# S7G7_footprint_simplified_w_ethernet_v1p.net
KiCad netlist of a schematic drawn in EAGLE
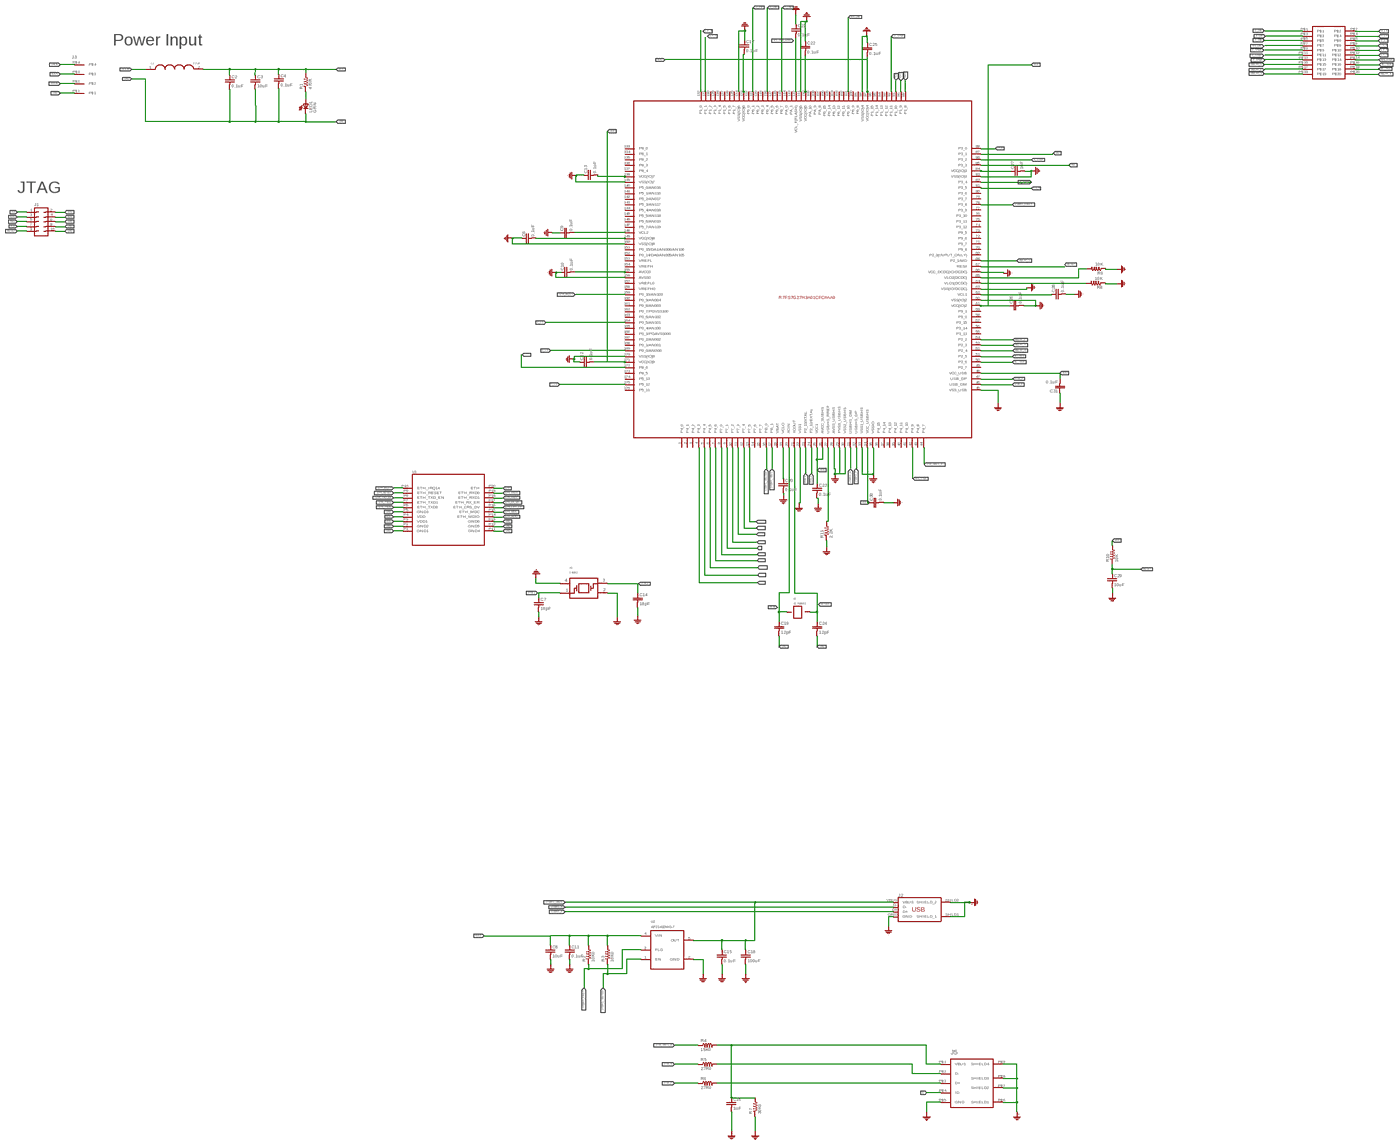
[diagram p0: schematic, sheet 1, overview]
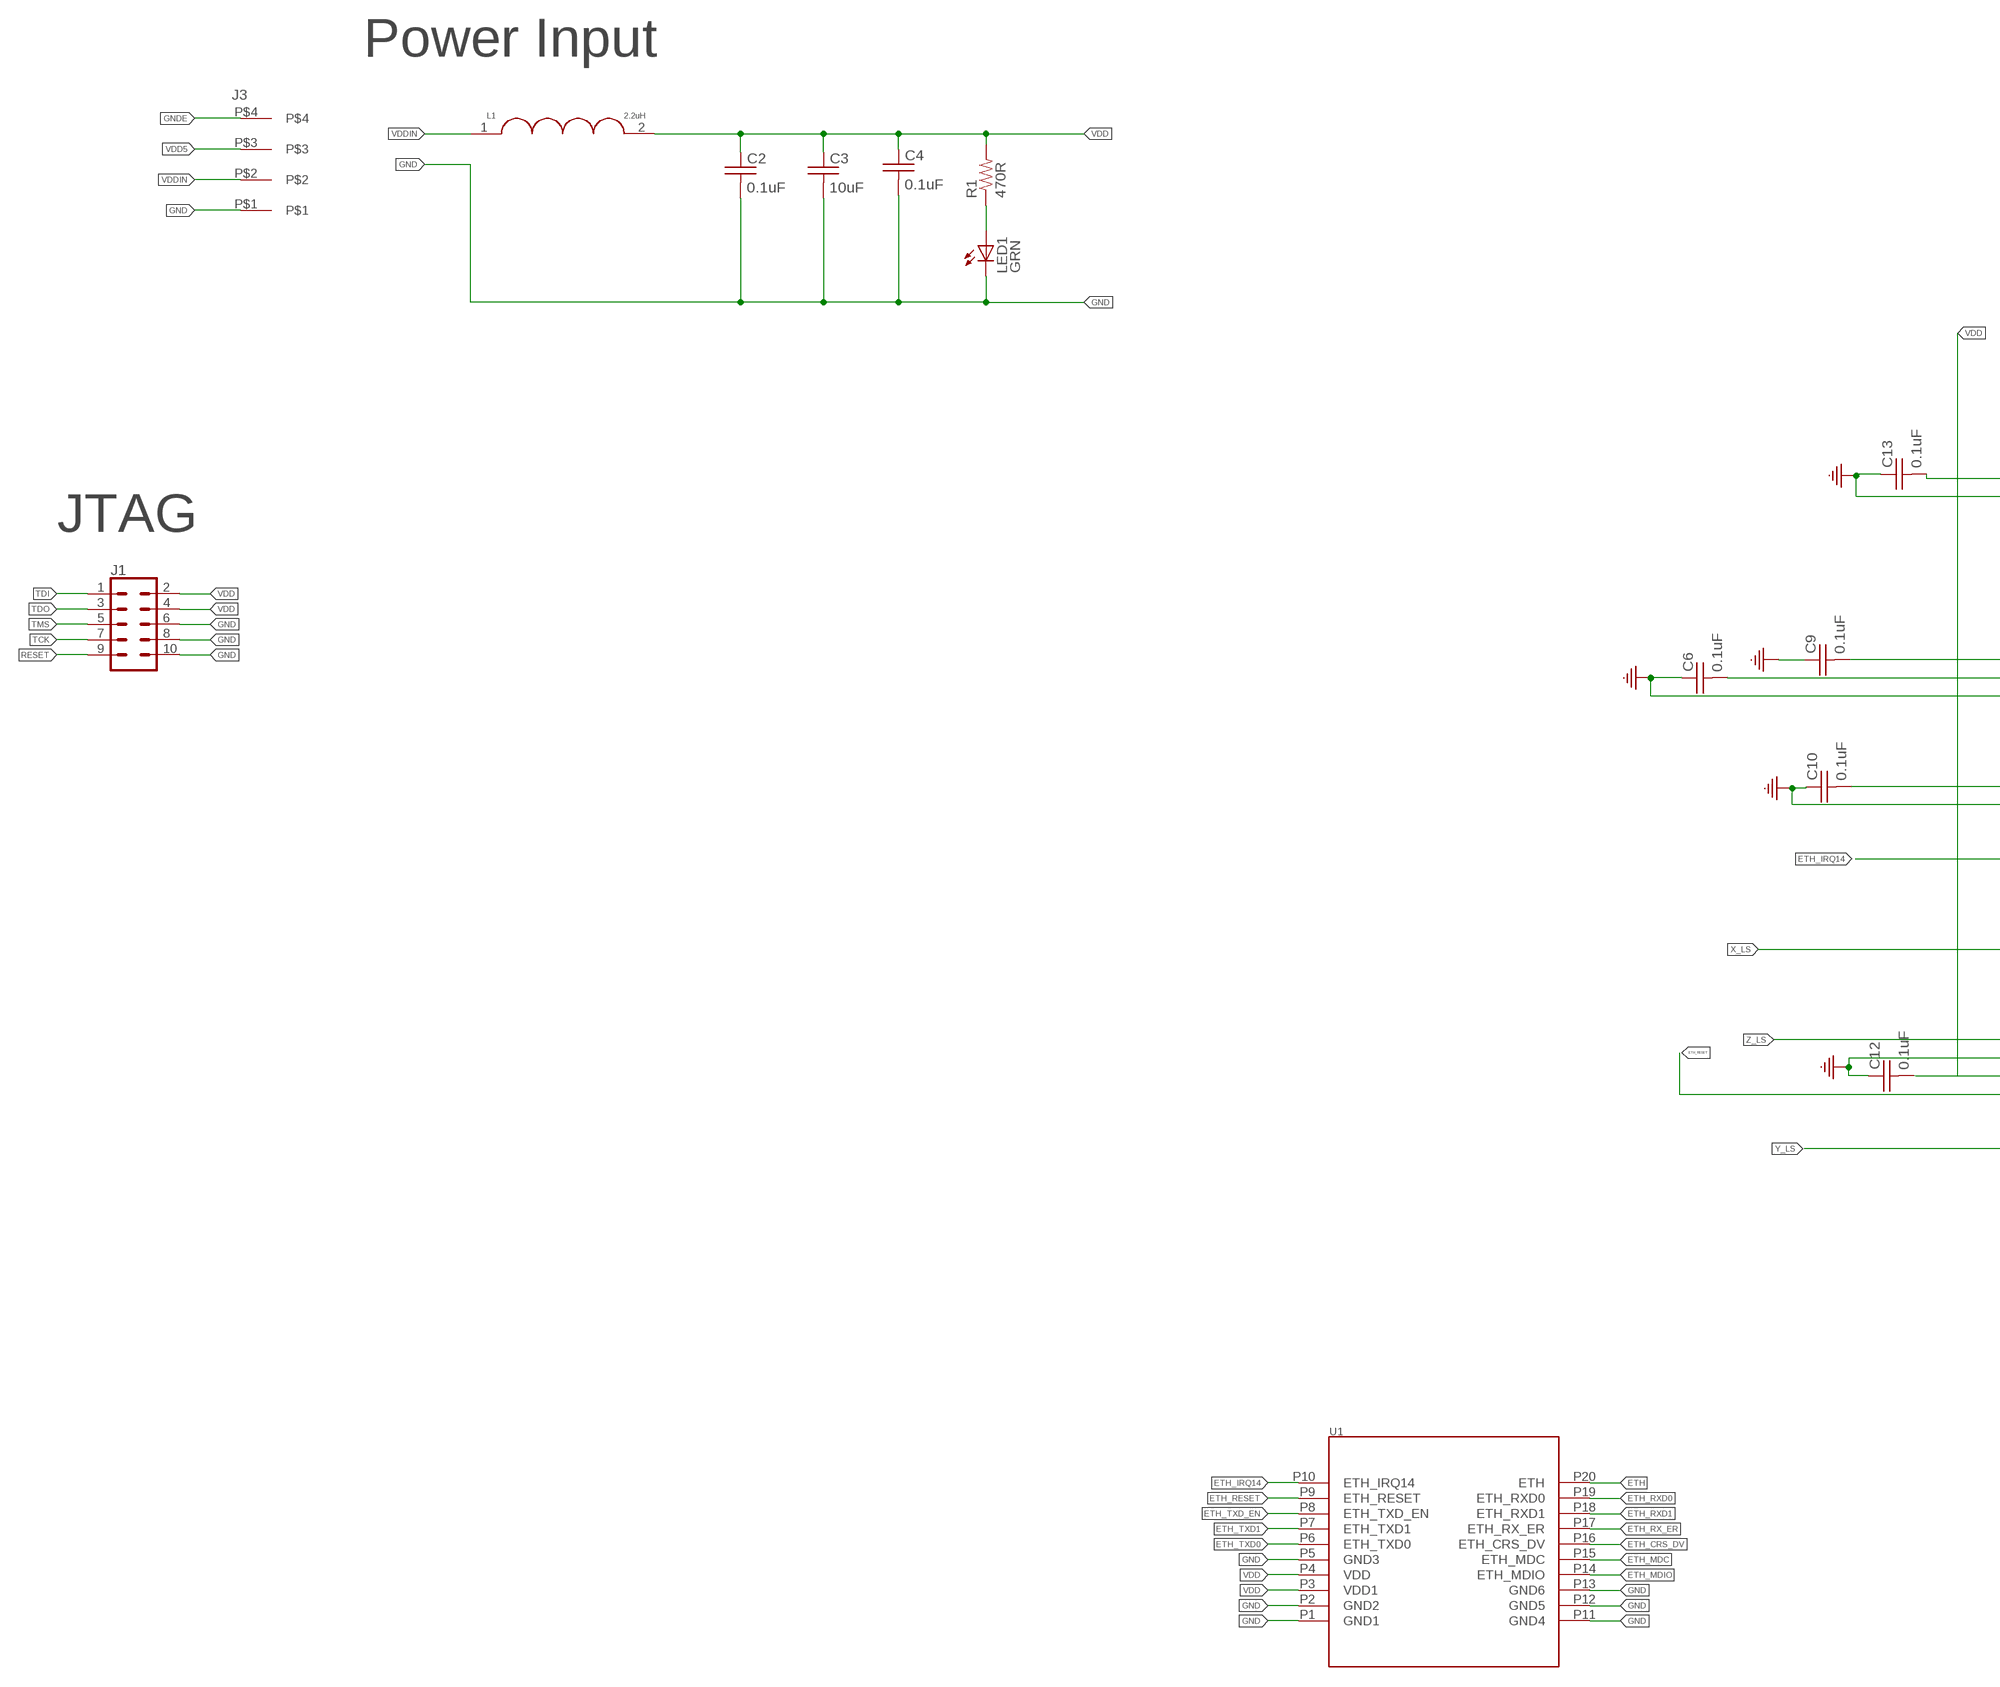
[diagram p1: schematic, sheet 1, part 1 of 4]
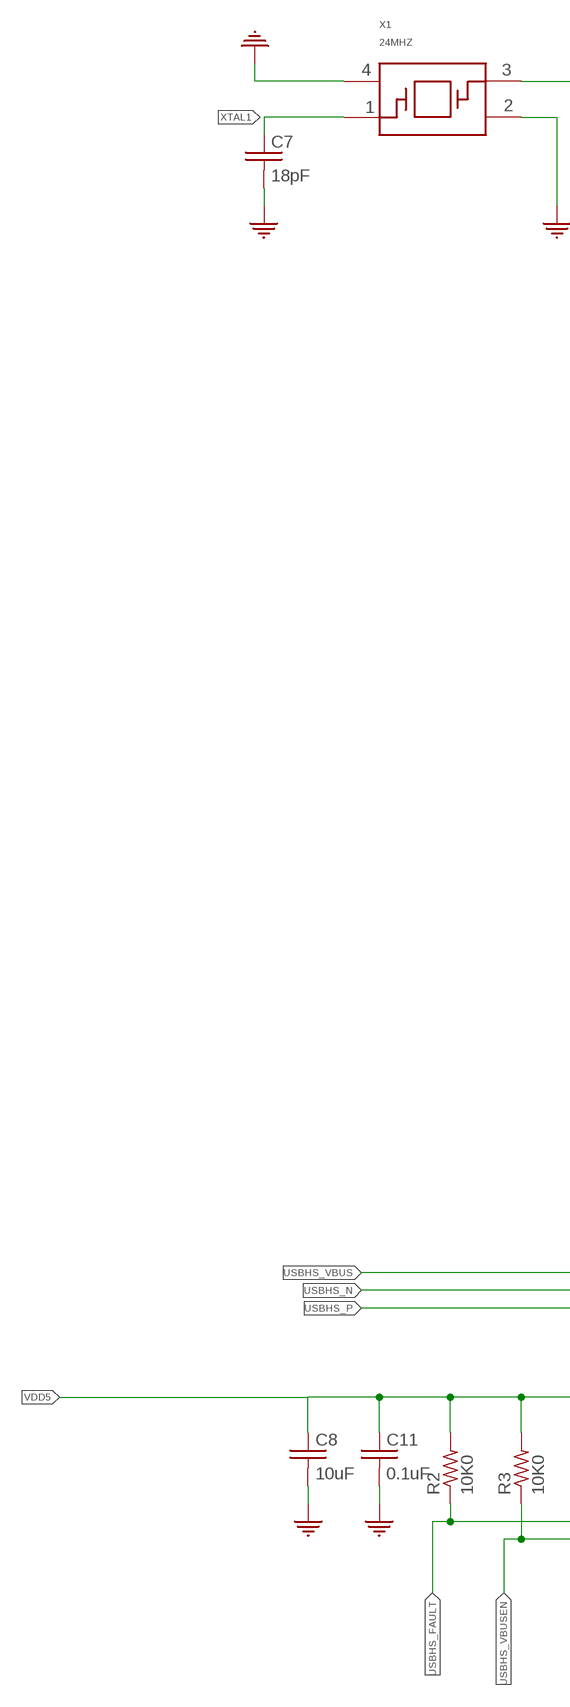
[diagram p2: schematic, sheet 1, part 2 of 4]
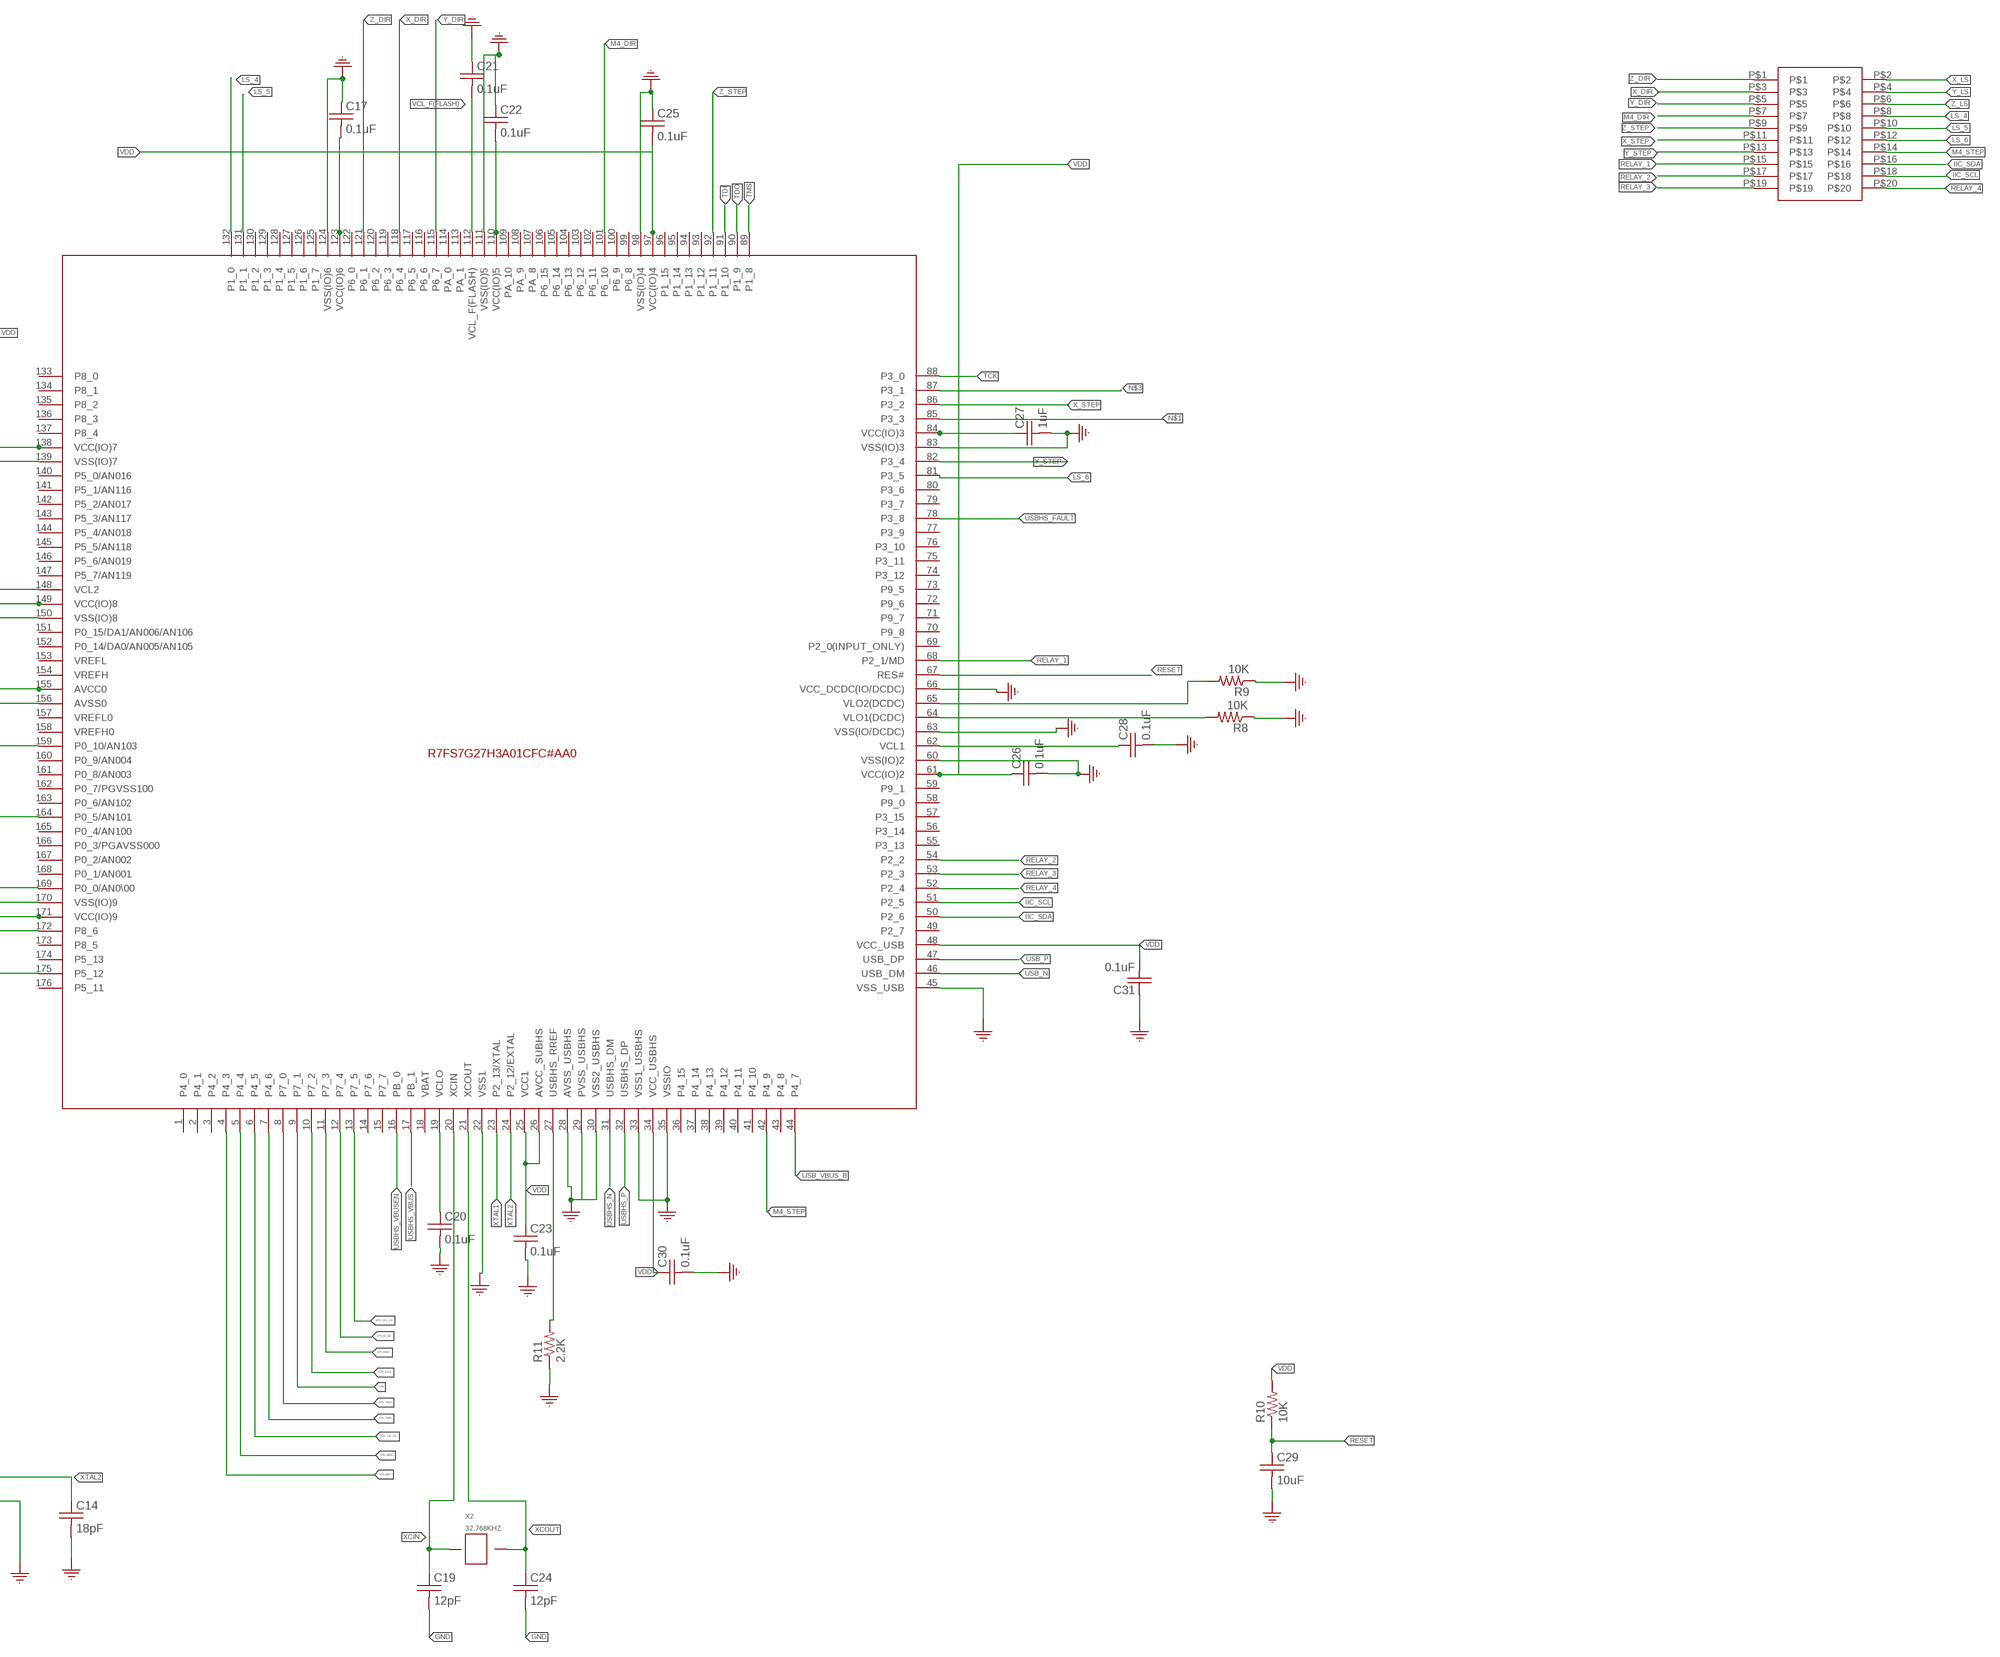
[diagram p3: schematic, sheet 1, part 3 of 4]
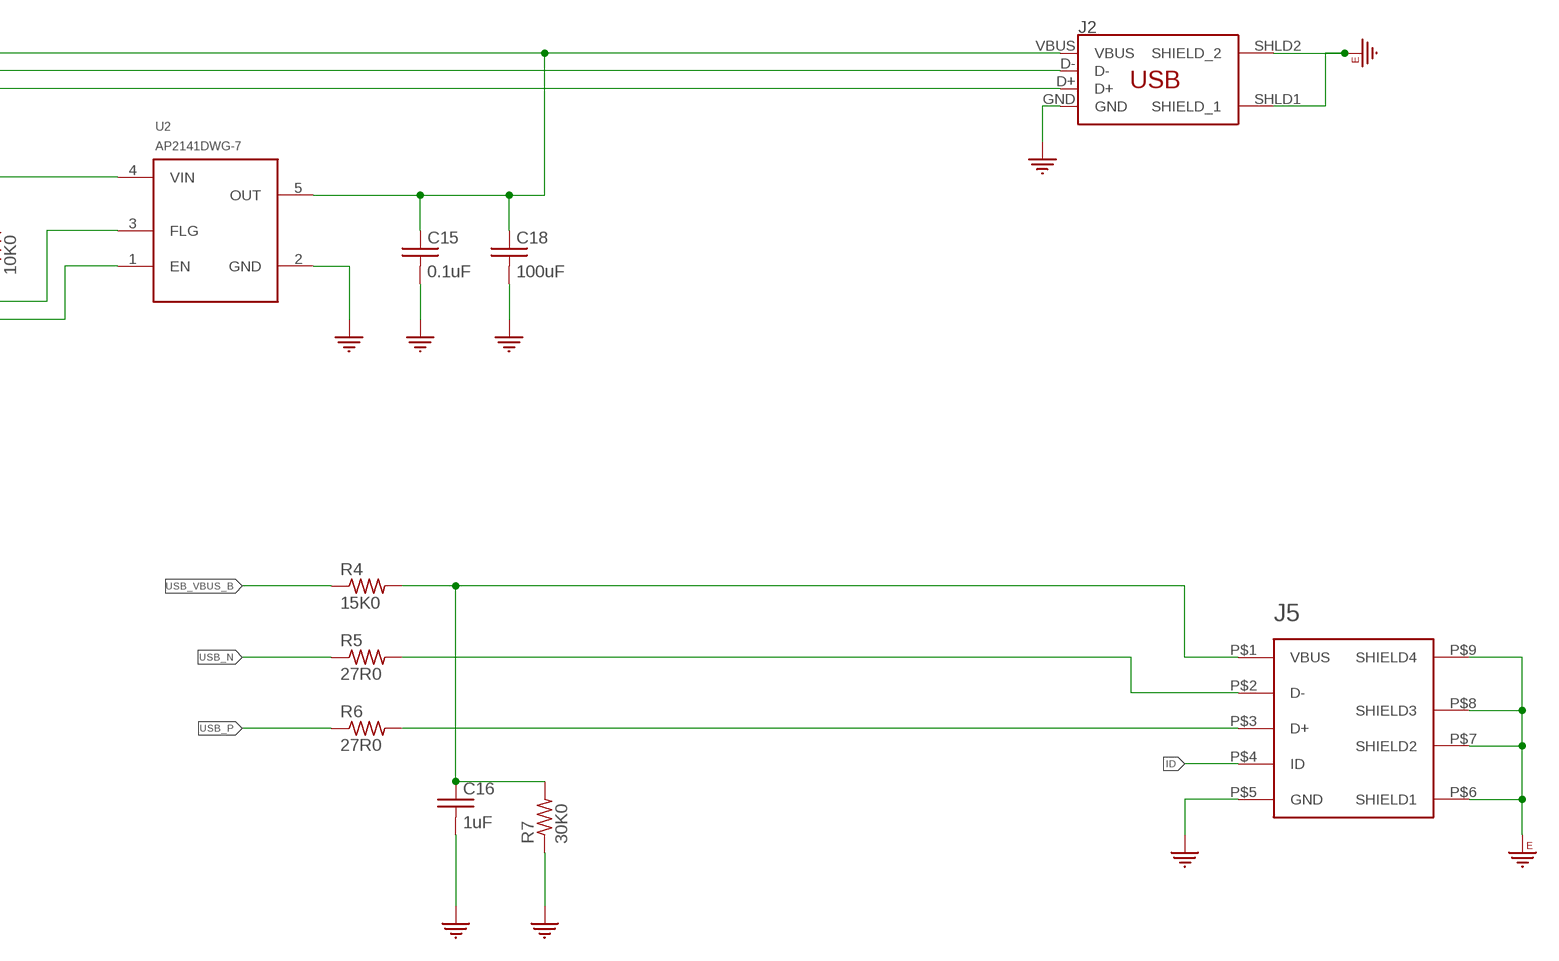
[diagram p4: schematic, sheet 1, part 4 of 4]

(export (version "E")
  (design (tool "Eeschema 10.0.6"))
  (components
    (comp (ref "C2")
      (value "0.1uF")
      (footprint "eagle-import:0402")
      (libsource (lib "eagle-import") (part "C_0402"))
    )
    (comp (ref "C3")
      (value "10uF")
      (footprint "eagle-import:0402")
      (libsource (lib "eagle-import") (part "C_0402"))
    )
    (comp (ref "C4")
      (value "0.1uF")
      (footprint "eagle-import:0402")
      (libsource (lib "eagle-import") (part "C_0402"))
    )
    (comp (ref "C6")
      (value "0.1uF")
      (footprint "eagle-import:0402")
      (libsource (lib "eagle-import") (part "C_0402"))
    )
    (comp (ref "C7")
      (value "18pF")
      (footprint "eagle-import:0402")
      (libsource (lib "eagle-import") (part "C_0402"))
    )
    (comp (ref "C8")
      (value "10uF")
      (footprint "eagle-import:0402")
      (libsource (lib "eagle-import") (part "C_0402"))
    )
    (comp (ref "C9")
      (value "0.1uF")
      (footprint "eagle-import:0402")
      (libsource (lib "eagle-import") (part "C_0402"))
    )
    (comp (ref "C10")
      (value "0.1uF")
      (footprint "eagle-import:0402")
      (libsource (lib "eagle-import") (part "C_0402"))
    )
    (comp (ref "C11")
      (value "0.1uF")
      (footprint "eagle-import:0402")
      (libsource (lib "eagle-import") (part "C_0402"))
    )
    (comp (ref "C12")
      (value "0.1uF")
      (footprint "eagle-import:0402")
      (libsource (lib "eagle-import") (part "C_0402"))
    )
    (comp (ref "C13")
      (value "0.1uF")
      (footprint "eagle-import:0402")
      (libsource (lib "eagle-import") (part "C_0402"))
    )
    (comp (ref "C14")
      (value "18pF")
      (footprint "eagle-import:0402")
      (libsource (lib "eagle-import") (part "C_0402"))
    )
    (comp (ref "C15")
      (value "0.1uF")
      (footprint "eagle-import:0402")
      (libsource (lib "eagle-import") (part "C_0402"))
    )
    (comp (ref "C16")
      (value "1uF")
      (footprint "eagle-import:0402")
      (libsource (lib "eagle-import") (part "C_0402"))
    )
    (comp (ref "C17")
      (value "0.1uF")
      (footprint "eagle-import:0402")
      (libsource (lib "eagle-import") (part "C_0402"))
    )
    (comp (ref "C18")
      (value "100uF")
      (footprint "eagle-import:C1210")
      (libsource (lib "eagle-import") (part "C_1210"))
    )
    (comp (ref "C19")
      (value "12pF")
      (footprint "eagle-import:0402")
      (libsource (lib "eagle-import") (part "C_0402"))
    )
    (comp (ref "C20")
      (value "0.1uF")
      (footprint "eagle-import:0402")
      (libsource (lib "eagle-import") (part "C_0402"))
    )
    (comp (ref "C21")
      (value "0.1uF")
      (footprint "eagle-import:0402")
      (libsource (lib "eagle-import") (part "C_0402"))
    )
    (comp (ref "C22")
      (value "0.1uF")
      (footprint "eagle-import:0402")
      (libsource (lib "eagle-import") (part "C_0402"))
    )
    (comp (ref "C23")
      (value "0.1uF")
      (footprint "eagle-import:0402")
      (libsource (lib "eagle-import") (part "C_0402"))
    )
    (comp (ref "C24")
      (value "12pF")
      (footprint "eagle-import:0402")
      (libsource (lib "eagle-import") (part "C_0402"))
    )
    (comp (ref "C25")
      (value "0.1uF")
      (footprint "eagle-import:0402")
      (libsource (lib "eagle-import") (part "C_0402"))
    )
    (comp (ref "C26")
      (value "0.1uF")
      (footprint "eagle-import:0402")
      (libsource (lib "eagle-import") (part "C_0402"))
    )
    (comp (ref "C27")
      (value "1uF")
      (footprint "eagle-import:0402")
      (libsource (lib "eagle-import") (part "C_0402"))
    )
    (comp (ref "C28")
      (value "0.1uF")
      (footprint "eagle-import:0402")
      (libsource (lib "eagle-import") (part "C_0402"))
    )
    (comp (ref "C29")
      (value "10uF")
      (footprint "eagle-import:0402")
      (libsource (lib "eagle-import") (part "C_0402"))
    )
    (comp (ref "C30")
      (value "0.1uF")
      (footprint "eagle-import:0402")
      (libsource (lib "eagle-import") (part "C_0402"))
    )
    (comp (ref "C31")
      (value "0.1uF")
      (footprint "eagle-import:0402")
      (libsource (lib "eagle-import") (part "C_0402"))
    )
    (comp (ref "J1")
      (value "CONN_05X2PTH")
      (footprint "eagle-import:2X5")
      (libsource (lib "eagle-import") (part "CONN_05X2PTH"))
    )
    (comp (ref "J2")
      (value "USB_A")
      (footprint "eagle-import:USB_A_SMT")
      (libsource (lib "eagle-import") (part "USB_A"))
    )
    (comp (ref "J3")
      (value "3.81MM_1_X_4_RT_ANGLE_PLUG_HEADER")
      (footprint "eagle-import:1X4_3.81MM_PITCH")
      (libsource (lib "eagle-import") (part "3.81MM_1_X_4_RT_ANGLE_PLUG_HEADER"))
    )
    (comp (ref "J4")
      (value "2_X_10_HEADER_GENERIC")
      (footprint "eagle-import:2_X_10_.1_INCH")
      (libsource (lib "eagle-import") (part "2_X_10_HEADER_GENERIC"))
    )
    (comp (ref "J5")
      (value "USB_MICRO-B")
      (footprint "eagle-import:USB_MICRO-B")
      (libsource (lib "eagle-import") (part "USB_MICRO-B"))
    )
    (comp (ref "L1")
      (value "2.2uH")
      (footprint "eagle-import:1008_(2520_METRIC)")
      (libsource (lib "eagle-import") (part "INDUCTOR_1008_2.2_MH_1.3A"))
    )
    (comp (ref "LED1")
      (value "LED_0805_GREEN")
      (footprint "eagle-import:LED_0805_GREEN")
      (libsource (lib "eagle-import") (part "LED_0805_GREEN"))
    )
    (comp (ref "R1")
      (value "470R")
      (footprint "eagle-import:0402")
      (libsource (lib "eagle-import") (part "R_0402"))
    )
    (comp (ref "R2")
      (value "10K0")
      (footprint "eagle-import:0402")
      (libsource (lib "eagle-import") (part "R_0402"))
    )
    (comp (ref "R3")
      (value "10K0")
      (footprint "eagle-import:0402")
      (libsource (lib "eagle-import") (part "R_0402"))
    )
    (comp (ref "R4")
      (value "15K0")
      (footprint "eagle-import:0402")
      (libsource (lib "eagle-import") (part "R_0402"))
    )
    (comp (ref "R5")
      (value "27R0")
      (footprint "eagle-import:0402")
      (libsource (lib "eagle-import") (part "R_0402"))
    )
    (comp (ref "R6")
      (value "27R0")
      (footprint "eagle-import:0402")
      (libsource (lib "eagle-import") (part "R_0402"))
    )
    (comp (ref "R7")
      (value "30K0")
      (footprint "eagle-import:0402")
      (libsource (lib "eagle-import") (part "R_0402"))
    )
    (comp (ref "R8")
      (value "10K")
      (footprint "eagle-import:0402")
      (libsource (lib "eagle-import") (part "R_0402"))
    )
    (comp (ref "R9")
      (value "10K")
      (footprint "eagle-import:0402")
      (libsource (lib "eagle-import") (part "R_0402"))
    )
    (comp (ref "R10")
      (value "10K")
      (footprint "eagle-import:0402")
      (libsource (lib "eagle-import") (part "R_0402"))
    )
    (comp (ref "R11")
      (value "2.2K")
      (footprint "eagle-import:0402")
      (libsource (lib "eagle-import") (part "R_0402"))
    )
    (comp (ref "U1")
      (value "ETHERNET_HAT")
      (footprint "eagle-import:ETHERNET_HAT")
      (libsource (lib "eagle-import") (part "ETHERNET_HAT"))
    )
    (comp (ref "U2")
      (value "AP2141DWG-5")
      (footprint "eagle-import:SOT-23-5")
      (libsource (lib "eagle-import") (part "AP2141DWG-5"))
    )
    (comp (ref "U5")
      (value "S7G2_X_176")
      (footprint "eagle-import:LQFP176_24X24")
      (libsource (lib "eagle-import") (part "S7G2_X_176"))
    )
    (comp (ref "X1")
      (value "24MHZ")
      (footprint "eagle-import:SMD_3225")
      (libsource (lib "eagle-import") (part "XTAL_24_MHZ"))
    )
    (comp (ref "X2")
      (value "32.768KHZ")
      (footprint "eagle-import:SMD_X_2_PADS")
      (libsource (lib "eagle-import") (part "XTAL_32.768KHZ"))
    )
  )
  (nets
    (net (code "1") (name "ETH") (class "Default")
      (node (ref "U1") (pin "P20") (pinfunction "ETH_P20") (pintype "bidirectional"))
      (node (ref "U5") (pin "9") (pinfunction "P7_1_9") (pintype "bidirectional"))
    )
    (net (code "2") (name "ETH_CRS_DV") (class "Default")
      (node (ref "U1") (pin "P16") (pinfunction "ETH_CRS_DV_P16") (pintype "bidirectional"))
      (node (ref "U5") (pin "13") (pinfunction "P7_5_13") (pintype "bidirectional"))
    )
    (net (code "3") (name "ETH_IRQ14") (class "Default")
      (node (ref "U1") (pin "P10") (pinfunction "ETH_IRQ14_P10") (pintype "bidirectional"))
      (node (ref "U5") (pin "159") (pinfunction "P0_10/AN103_159") (pintype "bidirectional"))
    )
    (net (code "4") (name "ETH_MDC") (class "Default")
      (node (ref "U1") (pin "P15") (pinfunction "ETH_MDC_P15") (pintype "bidirectional"))
      (node (ref "U5") (pin "4") (pinfunction "P4_3_4") (pintype "bidirectional"))
    )
    (net (code "5") (name "ETH_MDIO") (class "Default")
      (node (ref "U1") (pin "P14") (pinfunction "ETH_MDIO_P14") (pintype "bidirectional"))
      (node (ref "U5") (pin "5") (pinfunction "P4_4_5") (pintype "bidirectional"))
    )
    (net (code "6") (name "ETH_RESET") (class "Default")
      (node (ref "U1") (pin "P9") (pinfunction "ETH_RESET_P9") (pintype "bidirectional"))
      (node (ref "U5") (pin "172") (pinfunction "P8_6_172") (pintype "bidirectional"))
    )
    (net (code "7") (name "ETH_RXD0") (class "Default")
      (node (ref "U1") (pin "P19") (pinfunction "ETH_RXD0_P19") (pintype "bidirectional"))
      (node (ref "U5") (pin "10") (pinfunction "P7_2_10") (pintype "bidirectional"))
    )
    (net (code "8") (name "ETH_RXD1") (class "Default")
      (node (ref "U1") (pin "P18") (pinfunction "ETH_RXD1_P18") (pintype "bidirectional"))
      (node (ref "U5") (pin "11") (pinfunction "P7_3_11") (pintype "bidirectional"))
    )
    (net (code "9") (name "ETH_RX_ER") (class "Default")
      (node (ref "U1") (pin "P17") (pinfunction "ETH_RX_ER_P17") (pintype "bidirectional"))
      (node (ref "U5") (pin "12") (pinfunction "P7_4_12") (pintype "bidirectional"))
    )
    (net (code "10") (name "ETH_TXD0") (class "Default")
      (node (ref "U1") (pin "P6") (pinfunction "ETH_TXD0_P6") (pintype "bidirectional"))
      (node (ref "U5") (pin "8") (pinfunction "P7_0_8") (pintype "bidirectional"))
    )
    (net (code "11") (name "ETH_TXD1") (class "Default")
      (node (ref "U1") (pin "P7") (pinfunction "ETH_TXD1_P7") (pintype "bidirectional"))
      (node (ref "U5") (pin "7") (pinfunction "P4_6_7") (pintype "bidirectional"))
    )
    (net (code "12") (name "ETH_TXD_EN") (class "Default")
      (node (ref "U1") (pin "P8") (pinfunction "ETH_TXD_EN_P8") (pintype "bidirectional"))
      (node (ref "U5") (pin "6") (pinfunction "P4_5_6") (pintype "bidirectional"))
    )
    (net (code "13") (name "GND") (class "Default")
      (node (ref "C10") (pin "P$1") (pinfunction "1_P$1") (pintype "passive"))
      (node (ref "C11") (pin "P$2") (pinfunction "2_P$2") (pintype "passive"))
      (node (ref "C12") (pin "P$1") (pinfunction "1_P$1") (pintype "passive"))
      (node (ref "C13") (pin "P$1") (pinfunction "1_P$1") (pintype "passive"))
      (node (ref "C14") (pin "P$2") (pinfunction "2_P$2") (pintype "passive"))
      (node (ref "C15") (pin "P$2") (pinfunction "2_P$2") (pintype "passive"))
      (node (ref "C16") (pin "P$2") (pinfunction "2_P$2") (pintype "passive"))
      (node (ref "C17") (pin "P$1") (pinfunction "1_P$1") (pintype "passive"))
      (node (ref "C18") (pin "2") (pinfunction "2_2") (pintype "passive"))
      (node (ref "C19") (pin "P$2") (pinfunction "2_P$2") (pintype "passive"))
      (node (ref "C2") (pin "P$2") (pinfunction "2_P$2") (pintype "passive"))
      (node (ref "C20") (pin "P$2") (pinfunction "2_P$2") (pintype "passive"))
      (node (ref "C21") (pin "P$1") (pinfunction "1_P$1") (pintype "passive"))
      (node (ref "C22") (pin "P$1") (pinfunction "1_P$1") (pintype "passive"))
      (node (ref "C23") (pin "P$2") (pinfunction "2_P$2") (pintype "passive"))
      (node (ref "C24") (pin "P$2") (pinfunction "2_P$2") (pintype "passive"))
      (node (ref "C25") (pin "P$1") (pinfunction "1_P$1") (pintype "passive"))
      (node (ref "C26") (pin "P$2") (pinfunction "2_P$2") (pintype "passive"))
      (node (ref "C27") (pin "P$2") (pinfunction "2_P$2") (pintype "passive"))
      (node (ref "C28") (pin "P$2") (pinfunction "2_P$2") (pintype "passive"))
      (node (ref "C29") (pin "P$2") (pinfunction "2_P$2") (pintype "passive"))
      (node (ref "C3") (pin "P$2") (pinfunction "2_P$2") (pintype "passive"))
      (node (ref "C30") (pin "P$2") (pinfunction "2_P$2") (pintype "passive"))
      (node (ref "C31") (pin "P$1") (pinfunction "1_P$1") (pintype "passive"))
      (node (ref "C4") (pin "P$2") (pinfunction "2_P$2") (pintype "passive"))
      (node (ref "C6") (pin "P$1") (pinfunction "1_P$1") (pintype "passive"))
      (node (ref "C7") (pin "P$2") (pinfunction "2_P$2") (pintype "passive"))
      (node (ref "C8") (pin "P$2") (pinfunction "2_P$2") (pintype "passive"))
      (node (ref "C9") (pin "P$1") (pinfunction "1_P$1") (pintype "passive"))
      (node (ref "J1") (pin "10") (pinfunction "10_10") (pintype "passive"))
      (node (ref "J1") (pin "6") (pinfunction "6_6") (pintype "passive"))
      (node (ref "J1") (pin "8") (pinfunction "8_8") (pintype "passive"))
      (node (ref "J2") (pin "GND") (pinfunction "GND_GND") (pintype "power_in"))
      (node (ref "J3") (pin "P$1") (pinfunction "P$1_P$1") (pintype "bidirectional"))
      (node (ref "J5") (pin "P$5") (pinfunction "GND_P$5") (pintype "bidirectional"))
      (node (ref "LED1") (pin "C") (pinfunction "C_C") (pintype "passive"))
      (node (ref "R11") (pin "P$1") (pinfunction "1_P$1") (pintype "passive"))
      (node (ref "R7") (pin "P$1") (pinfunction "1_P$1") (pintype "passive"))
      (node (ref "R8") (pin "P$1") (pinfunction "1_P$1") (pintype "passive"))
      (node (ref "R9") (pin "P$1") (pinfunction "1_P$1") (pintype "passive"))
      (node (ref "U1") (pin "P1") (pinfunction "GND1_P1") (pintype "bidirectional"))
      (node (ref "U1") (pin "P11") (pinfunction "GND4_P11") (pintype "bidirectional"))
      (node (ref "U1") (pin "P12") (pinfunction "GND5_P12") (pintype "bidirectional"))
      (node (ref "U1") (pin "P13") (pinfunction "GND6_P13") (pintype "bidirectional"))
      (node (ref "U1") (pin "P2") (pinfunction "GND2_P2") (pintype "bidirectional"))
      (node (ref "U1") (pin "P5") (pinfunction "GND3_P5") (pintype "bidirectional"))
      (node (ref "U2") (pin "2") (pinfunction "GND_2") (pintype "input"))
      (node (ref "U5") (pin "111") (pinfunction "VSS(IO)5_111") (pintype "bidirectional"))
      (node (ref "U5") (pin "124") (pinfunction "VSS(IO)6_124") (pintype "bidirectional"))
      (node (ref "U5") (pin "139") (pinfunction "VSS(IO)7_139") (pintype "bidirectional"))
      (node (ref "U5") (pin "150") (pinfunction "VSS(IO)8_150") (pintype "bidirectional"))
      (node (ref "U5") (pin "156") (pinfunction "AVSS0_156") (pintype "bidirectional"))
      (node (ref "U5") (pin "170") (pinfunction "VSS(IO)9_170") (pintype "bidirectional"))
      (node (ref "U5") (pin "22") (pinfunction "VSS1_22") (pintype "bidirectional"))
      (node (ref "U5") (pin "28") (pinfunction "AVSS_USBHS_28") (pintype "bidirectional"))
      (node (ref "U5") (pin "29") (pinfunction "PVSS_USBHS_29") (pintype "bidirectional"))
      (node (ref "U5") (pin "30") (pinfunction "VSS2_USBHS_30") (pintype "bidirectional"))
      (node (ref "U5") (pin "33") (pinfunction "VSS1_USBHS_33") (pintype "bidirectional"))
      (node (ref "U5") (pin "35") (pinfunction "VSSIO_35") (pintype "bidirectional"))
      (node (ref "U5") (pin "45") (pinfunction "VSS_USB_45") (pintype "bidirectional"))
      (node (ref "U5") (pin "60") (pinfunction "VSS(IO)2_60") (pintype "bidirectional"))
      (node (ref "U5") (pin "63") (pinfunction "VSS(IO/DCDC)_63") (pintype "bidirectional"))
      (node (ref "U5") (pin "66") (pinfunction "VCC_DCDC(IO/DCDC)_66") (pintype "bidirectional"))
      (node (ref "U5") (pin "83") (pinfunction "VSS(IO)3_83") (pintype "bidirectional"))
      (node (ref "U5") (pin "98") (pinfunction "VSS(IO)4_98") (pintype "bidirectional"))
      (node (ref "X1") (pin "2") (pinfunction "2_2") (pintype "bidirectional"))
      (node (ref "X1") (pin "4") (pinfunction "4_4") (pintype "bidirectional"))
    )
    (net (code "14") (name "GNDE") (class "Default")
      (node (ref "J2") (pin "SHLD1") (pinfunction "SHIELD_1_SHLD1") (pintype "bidirectional"))
      (node (ref "J2") (pin "SHLD2") (pinfunction "SHIELD_2_SHLD2") (pintype "bidirectional"))
      (node (ref "J3") (pin "P$4") (pinfunction "P$4_P$4") (pintype "bidirectional"))
      (node (ref "J5") (pin "P$6") (pinfunction "SHIELD1_P$6") (pintype "bidirectional"))
      (node (ref "J5") (pin "P$7") (pinfunction "SHIELD2_P$7") (pintype "bidirectional"))
      (node (ref "J5") (pin "P$8") (pinfunction "SHIELD3_P$8") (pintype "bidirectional"))
      (node (ref "J5") (pin "P$9") (pinfunction "SHIELD4_P$9") (pintype "bidirectional"))
    )
    (net (code "15") (name "ID") (class "Default")
      (node (ref "J5") (pin "P$4") (pinfunction "ID_P$4") (pintype "bidirectional"))
    )
    (net (code "16") (name "IIC_SCL") (class "Default")
      (node (ref "J4") (pin "P$18") (pinfunction "P$18_P$18") (pintype "bidirectional"))
      (node (ref "U5") (pin "51") (pinfunction "P2_5_51") (pintype "bidirectional"))
    )
    (net (code "17") (name "IIC_SDA") (class "Default")
      (node (ref "J4") (pin "P$16") (pinfunction "P$16_P$16") (pintype "bidirectional"))
      (node (ref "U5") (pin "50") (pinfunction "P2_6_50") (pintype "bidirectional"))
    )
    (net (code "18") (name "LS_4") (class "Default")
      (node (ref "J4") (pin "P$8") (pinfunction "P$8_P$8") (pintype "bidirectional"))
      (node (ref "U5") (pin "132") (pinfunction "P1_0_132") (pintype "bidirectional"))
    )
    (net (code "19") (name "LS_5") (class "Default")
      (node (ref "J4") (pin "P$10") (pinfunction "P$10_P$10") (pintype "bidirectional"))
      (node (ref "U5") (pin "131") (pinfunction "P1_1_131") (pintype "bidirectional"))
    )
    (net (code "20") (name "LS_6") (class "Default")
      (node (ref "J4") (pin "P$12") (pinfunction "P$12_P$12") (pintype "bidirectional"))
      (node (ref "U5") (pin "81") (pinfunction "P3_5_81") (pintype "bidirectional"))
    )
    (net (code "21") (name "M4_DIR") (class "Default")
      (node (ref "J4") (pin "P$7") (pinfunction "P$7_P$7") (pintype "bidirectional"))
      (node (ref "U5") (pin "101") (pinfunction "P6_10_101") (pintype "bidirectional"))
    )
    (net (code "22") (name "M4_STEP") (class "Default")
      (node (ref "J4") (pin "P$14") (pinfunction "P$14_P$14") (pintype "bidirectional"))
      (node (ref "U5") (pin "42") (pinfunction "P4_9_42") (pintype "bidirectional"))
    )
    (net (code "23") (name "N$1") (class "Default")
      (node (ref "U5") (pin "85") (pinfunction "P3_3_85") (pintype "bidirectional"))
    )
    (net (code "24") (name "N$3") (class "Default")
      (node (ref "U5") (pin "87") (pinfunction "P3_1_87") (pintype "bidirectional"))
    )
    (net (code "25") (name "Net-(C9-2)") (class "Default")
      (node (ref "C9") (pin "P$2") (pinfunction "2_P$2") (pintype "passive"))
      (node (ref "U5") (pin "148") (pinfunction "VCL2_148") (pintype "bidirectional"))
    )
    (net (code "26") (name "Net-(C16-1)") (class "Default")
      (node (ref "C16") (pin "P$1") (pinfunction "1_P$1") (pintype "passive"))
      (node (ref "J5") (pin "P$1") (pinfunction "VBUS_P$1") (pintype "bidirectional"))
      (node (ref "R4") (pin "P$2") (pinfunction "2_P$2") (pintype "passive"))
      (node (ref "R7") (pin "P$2") (pinfunction "2_P$2") (pintype "passive"))
    )
    (net (code "27") (name "Net-(C20-1)") (class "Default")
      (node (ref "C20") (pin "P$1") (pinfunction "1_P$1") (pintype "passive"))
      (node (ref "U5") (pin "19") (pinfunction "VCLO_19") (pintype "bidirectional"))
    )
    (net (code "28") (name "Net-(C28-1)") (class "Default")
      (node (ref "C28") (pin "P$1") (pinfunction "1_P$1") (pintype "passive"))
      (node (ref "U5") (pin "62") (pinfunction "VCL1_62") (pintype "bidirectional"))
    )
    (net (code "29") (name "Net-(J5-D+)") (class "Default")
      (node (ref "J5") (pin "P$3") (pinfunction "D+_P$3") (pintype "bidirectional"))
      (node (ref "R6") (pin "P$2") (pinfunction "2_P$2") (pintype "passive"))
    )
    (net (code "30") (name "Net-(J5-D-)") (class "Default")
      (node (ref "J5") (pin "P$2") (pinfunction "D-_P$2") (pintype "bidirectional"))
      (node (ref "R5") (pin "P$2") (pinfunction "2_P$2") (pintype "passive"))
    )
    (net (code "31") (name "Net-(R1-1)") (class "Default")
      (node (ref "LED1") (pin "A") (pinfunction "A_A") (pintype "passive"))
      (node (ref "R1") (pin "P$1") (pinfunction "1_P$1") (pintype "passive"))
    )
    (net (code "32") (name "Net-(R8-2)") (class "Default")
      (node (ref "R8") (pin "P$2") (pinfunction "2_P$2") (pintype "passive"))
      (node (ref "U5") (pin "64") (pinfunction "VLO1(DCDC)_64") (pintype "bidirectional"))
    )
    (net (code "33") (name "Net-(R9-2)") (class "Default")
      (node (ref "R9") (pin "P$2") (pinfunction "2_P$2") (pintype "passive"))
      (node (ref "U5") (pin "65") (pinfunction "VLO2(DCDC)_65") (pintype "bidirectional"))
    )
    (net (code "34") (name "Net-(R11-2)") (class "Default")
      (node (ref "R11") (pin "P$2") (pinfunction "2_P$2") (pintype "passive"))
      (node (ref "U5") (pin "27") (pinfunction "USBHS_RREF_27") (pintype "bidirectional"))
    )
    (net (code "35") (name "RELAY_1") (class "Default")
      (node (ref "J4") (pin "P$15") (pinfunction "P$15_P$15") (pintype "bidirectional"))
      (node (ref "U5") (pin "68") (pinfunction "P2_1/MD_68") (pintype "bidirectional"))
    )
    (net (code "36") (name "RELAY_2") (class "Default")
      (node (ref "J4") (pin "P$17") (pinfunction "P$17_P$17") (pintype "bidirectional"))
      (node (ref "U5") (pin "54") (pinfunction "P2_2_54") (pintype "bidirectional"))
    )
    (net (code "37") (name "RELAY_3") (class "Default")
      (node (ref "J4") (pin "P$19") (pinfunction "P$19_P$19") (pintype "bidirectional"))
      (node (ref "U5") (pin "53") (pinfunction "P2_3_53") (pintype "bidirectional"))
    )
    (net (code "38") (name "RELAY_4") (class "Default")
      (node (ref "J4") (pin "P$20") (pinfunction "P$20_P$20") (pintype "bidirectional"))
      (node (ref "U5") (pin "52") (pinfunction "P2_4_52") (pintype "bidirectional"))
    )
    (net (code "39") (name "RESET") (class "Default")
      (node (ref "C29") (pin "P$1") (pinfunction "1_P$1") (pintype "passive"))
      (node (ref "J1") (pin "9") (pinfunction "9_9") (pintype "passive"))
      (node (ref "R10") (pin "P$1") (pinfunction "1_P$1") (pintype "passive"))
      (node (ref "U5") (pin "67") (pinfunction "RES#_67") (pintype "bidirectional"))
    )
    (net (code "40") (name "TCK") (class "Default")
      (node (ref "J1") (pin "7") (pinfunction "7_7") (pintype "passive"))
      (node (ref "U5") (pin "88") (pinfunction "P3_0_88") (pintype "bidirectional"))
    )
    (net (code "41") (name "TDI") (class "Default")
      (node (ref "J1") (pin "1") (pinfunction "1_1") (pintype "passive"))
      (node (ref "U5") (pin "91") (pinfunction "P1_10_91") (pintype "bidirectional"))
    )
    (net (code "42") (name "TDO") (class "Default")
      (node (ref "J1") (pin "3") (pinfunction "3_3") (pintype "passive"))
      (node (ref "U5") (pin "90") (pinfunction "P1_9_90") (pintype "bidirectional"))
    )
    (net (code "43") (name "TMS") (class "Default")
      (node (ref "J1") (pin "5") (pinfunction "5_5") (pintype "passive"))
      (node (ref "U5") (pin "89") (pinfunction "P1_8_89") (pintype "bidirectional"))
    )
    (net (code "44") (name "USBHS_FAULT") (class "Default")
      (node (ref "R2") (pin "P$1") (pinfunction "1_P$1") (pintype "passive"))
      (node (ref "U2") (pin "3") (pinfunction "FLG_3") (pintype "input"))
      (node (ref "U5") (pin "78") (pinfunction "P3_8_78") (pintype "bidirectional"))
    )
    (net (code "45") (name "USBHS_N") (class "Default")
      (node (ref "J2") (pin "D-") (pinfunction "D-_D-") (pintype "bidirectional"))
      (node (ref "U5") (pin "31") (pinfunction "USBHS_DM_31") (pintype "bidirectional"))
    )
    (net (code "46") (name "USBHS_P") (class "Default")
      (node (ref "J2") (pin "D+") (pinfunction "D+_D+") (pintype "bidirectional"))
      (node (ref "U5") (pin "32") (pinfunction "USBHS_DP_32") (pintype "bidirectional"))
    )
    (net (code "47") (name "USBHS_VBUS") (class "Default")
      (node (ref "C15") (pin "P$1") (pinfunction "1_P$1") (pintype "passive"))
      (node (ref "C18") (pin "1") (pinfunction "1_1") (pintype "passive"))
      (node (ref "J2") (pin "VBUS") (pinfunction "VBUS_VBUS") (pintype "power_in"))
      (node (ref "U2") (pin "5") (pinfunction "OUT_5") (pintype "input"))
      (node (ref "U5") (pin "17") (pinfunction "PB_1_17") (pintype "bidirectional"))
    )
    (net (code "48") (name "USBHS_VBUSEN") (class "Default")
      (node (ref "R3") (pin "P$1") (pinfunction "1_P$1") (pintype "passive"))
      (node (ref "U2") (pin "1") (pinfunction "EN_1") (pintype "input"))
      (node (ref "U5") (pin "16") (pinfunction "PB_0_16") (pintype "bidirectional"))
    )
    (net (code "49") (name "USB_N") (class "Default")
      (node (ref "R5") (pin "P$1") (pinfunction "1_P$1") (pintype "passive"))
      (node (ref "U5") (pin "46") (pinfunction "USB_DM_46") (pintype "bidirectional"))
    )
    (net (code "50") (name "USB_P") (class "Default")
      (node (ref "R6") (pin "P$1") (pinfunction "1_P$1") (pintype "passive"))
      (node (ref "U5") (pin "47") (pinfunction "USB_DP_47") (pintype "bidirectional"))
    )
    (net (code "51") (name "USB_VBUS_B") (class "Default")
      (node (ref "R4") (pin "P$1") (pinfunction "1_P$1") (pintype "passive"))
      (node (ref "U5") (pin "44") (pinfunction "P4_7_44") (pintype "bidirectional"))
    )
    (net (code "52") (name "VCL_F(FLASH)") (class "Default")
      (node (ref "C21") (pin "P$2") (pinfunction "2_P$2") (pintype "passive"))
      (node (ref "U5") (pin "112") (pinfunction "VCL_F(FLASH)_112") (pintype "bidirectional"))
    )
    (net (code "53") (name "VDD") (class "Default")
      (node (ref "C10") (pin "P$2") (pinfunction "2_P$2") (pintype "passive"))
      (node (ref "C12") (pin "P$2") (pinfunction "2_P$2") (pintype "passive"))
      (node (ref "C13") (pin "P$2") (pinfunction "2_P$2") (pintype "passive"))
      (node (ref "C17") (pin "P$2") (pinfunction "2_P$2") (pintype "passive"))
      (node (ref "C2") (pin "P$1") (pinfunction "1_P$1") (pintype "passive"))
      (node (ref "C22") (pin "P$2") (pinfunction "2_P$2") (pintype "passive"))
      (node (ref "C23") (pin "P$1") (pinfunction "1_P$1") (pintype "passive"))
      (node (ref "C25") (pin "P$2") (pinfunction "2_P$2") (pintype "passive"))
      (node (ref "C26") (pin "P$1") (pinfunction "1_P$1") (pintype "passive"))
      (node (ref "C27") (pin "P$1") (pinfunction "1_P$1") (pintype "passive"))
      (node (ref "C3") (pin "P$1") (pinfunction "1_P$1") (pintype "passive"))
      (node (ref "C30") (pin "P$1") (pinfunction "1_P$1") (pintype "passive"))
      (node (ref "C31") (pin "P$2") (pinfunction "2_P$2") (pintype "passive"))
      (node (ref "C4") (pin "P$1") (pinfunction "1_P$1") (pintype "passive"))
      (node (ref "C6") (pin "P$2") (pinfunction "2_P$2") (pintype "passive"))
      (node (ref "J1") (pin "2") (pinfunction "2_2") (pintype "passive"))
      (node (ref "J1") (pin "4") (pinfunction "4_4") (pintype "passive"))
      (node (ref "L1") (pin "2") (pinfunction "P$2_2") (pintype "bidirectional"))
      (node (ref "R1") (pin "P$2") (pinfunction "2_P$2") (pintype "passive"))
      (node (ref "R10") (pin "P$2") (pinfunction "2_P$2") (pintype "passive"))
      (node (ref "U1") (pin "P3") (pinfunction "VDD1_P3") (pintype "bidirectional"))
      (node (ref "U1") (pin "P4") (pinfunction "VDD_P4") (pintype "bidirectional"))
      (node (ref "U5") (pin "110") (pinfunction "VCC(IO)5_110") (pintype "bidirectional"))
      (node (ref "U5") (pin "123") (pinfunction "VCC(IO)6_123") (pintype "bidirectional"))
      (node (ref "U5") (pin "138") (pinfunction "VCC(IO)7_138") (pintype "bidirectional"))
      (node (ref "U5") (pin "149") (pinfunction "VCC(IO)8_149") (pintype "bidirectional"))
      (node (ref "U5") (pin "155") (pinfunction "AVCC0_155") (pintype "bidirectional"))
      (node (ref "U5") (pin "171") (pinfunction "VCC(IO)9_171") (pintype "bidirectional"))
      (node (ref "U5") (pin "25") (pinfunction "VCC1_25") (pintype "bidirectional"))
      (node (ref "U5") (pin "26") (pinfunction "AVCC_SUBHS_26") (pintype "bidirectional"))
      (node (ref "U5") (pin "34") (pinfunction "VCC_USBHS_34") (pintype "bidirectional"))
      (node (ref "U5") (pin "48") (pinfunction "VCC_USB_48") (pintype "bidirectional"))
      (node (ref "U5") (pin "61") (pinfunction "VCC(IO)2_61") (pintype "bidirectional"))
      (node (ref "U5") (pin "84") (pinfunction "VCC(IO)3_84") (pintype "bidirectional"))
      (node (ref "U5") (pin "97") (pinfunction "VCC(IO)4_97") (pintype "bidirectional"))
    )
    (net (code "54") (name "VDD5") (class "Default")
      (node (ref "C11") (pin "P$1") (pinfunction "1_P$1") (pintype "passive"))
      (node (ref "C8") (pin "P$1") (pinfunction "1_P$1") (pintype "passive"))
      (node (ref "J3") (pin "P$3") (pinfunction "P$3_P$3") (pintype "bidirectional"))
      (node (ref "R2") (pin "P$2") (pinfunction "2_P$2") (pintype "passive"))
      (node (ref "R3") (pin "P$2") (pinfunction "2_P$2") (pintype "passive"))
      (node (ref "U2") (pin "4") (pinfunction "VIN_4") (pintype "input"))
    )
    (net (code "55") (name "VDDIN") (class "Default")
      (node (ref "J3") (pin "P$2") (pinfunction "P$2_P$2") (pintype "bidirectional"))
      (node (ref "L1") (pin "1") (pinfunction "P$1_1") (pintype "bidirectional"))
    )
    (net (code "56") (name "XCIN") (class "Default")
      (node (ref "C19") (pin "P$1") (pinfunction "1_P$1") (pintype "passive"))
      (node (ref "U5") (pin "20") (pinfunction "XCIN_20") (pintype "bidirectional"))
      (node (ref "X2") (pin "P$1") (pinfunction "P$1_P$1") (pintype "bidirectional"))
    )
    (net (code "57") (name "XCOUT") (class "Default")
      (node (ref "C24") (pin "P$1") (pinfunction "1_P$1") (pintype "passive"))
      (node (ref "U5") (pin "21") (pinfunction "XCOUT_21") (pintype "bidirectional"))
      (node (ref "X2") (pin "P$2") (pinfunction "P$2_P$2") (pintype "bidirectional"))
    )
    (net (code "58") (name "XTAL1") (class "Default")
      (node (ref "C7") (pin "P$1") (pinfunction "1_P$1") (pintype "passive"))
      (node (ref "U5") (pin "23") (pinfunction "P2_13/XTAL_23") (pintype "bidirectional"))
      (node (ref "X1") (pin "1") (pinfunction "1_1") (pintype "bidirectional"))
    )
    (net (code "59") (name "XTAL2") (class "Default")
      (node (ref "C14") (pin "P$1") (pinfunction "1_P$1") (pintype "passive"))
      (node (ref "U5") (pin "24") (pinfunction "P2_12/EXTAL_24") (pintype "bidirectional"))
      (node (ref "X1") (pin "3") (pinfunction "3_3") (pintype "bidirectional"))
    )
    (net (code "60") (name "X_DIR") (class "Default")
      (node (ref "J4") (pin "P$3") (pinfunction "P$3_P$3") (pintype "bidirectional"))
      (node (ref "U5") (pin "118") (pinfunction "P6_4_118") (pintype "bidirectional"))
    )
    (net (code "61") (name "X_LS") (class "Default")
      (node (ref "J4") (pin "P$2") (pinfunction "P$2_P$2") (pintype "bidirectional"))
      (node (ref "U5") (pin "164") (pinfunction "P0_5/AN101_164") (pintype "bidirectional"))
    )
    (net (code "62") (name "X_STEP") (class "Default")
      (node (ref "J4") (pin "P$11") (pinfunction "P$11_P$11") (pintype "bidirectional"))
      (node (ref "U5") (pin "86") (pinfunction "P3_2_86") (pintype "bidirectional"))
    )
    (net (code "63") (name "Y_DIR") (class "Default")
      (node (ref "J4") (pin "P$5") (pinfunction "P$5_P$5") (pintype "bidirectional"))
      (node (ref "U5") (pin "115") (pinfunction "P6_7_115") (pintype "bidirectional"))
    )
    (net (code "64") (name "Y_LS") (class "Default")
      (node (ref "J4") (pin "P$4") (pinfunction "P$4_P$4") (pintype "bidirectional"))
      (node (ref "U5") (pin "175") (pinfunction "P5_12_175") (pintype "bidirectional"))
    )
    (net (code "65") (name "Y_STEP") (class "Default")
      (node (ref "J4") (pin "P$13") (pinfunction "P$13_P$13") (pintype "bidirectional"))
      (node (ref "U5") (pin "82") (pinfunction "P3_4_82") (pintype "bidirectional"))
    )
    (net (code "66") (name "Z_DIR") (class "Default")
      (node (ref "J4") (pin "P$1") (pinfunction "P$1_P$1") (pintype "bidirectional"))
      (node (ref "U5") (pin "121") (pinfunction "P6_1_121") (pintype "bidirectional"))
    )
    (net (code "67") (name "Z_LS") (class "Default")
      (node (ref "J4") (pin "P$6") (pinfunction "P$6_P$6") (pintype "bidirectional"))
      (node (ref "U5") (pin "169") (pinfunction "P0_0/AN0\\00_169") (pintype "bidirectional"))
    )
    (net (code "68") (name "Z_STEP") (class "Default")
      (node (ref "J4") (pin "P$9") (pinfunction "P$9_P$9") (pintype "bidirectional"))
      (node (ref "U5") (pin "92") (pinfunction "P1_11_92") (pintype "bidirectional"))
    )
    (net (code "69") (name "unconnected-(U5-P0_1{slash}AN001-Pad168)") (class "Default")
      (node (ref "U5") (pin "168") (pinfunction "P0_1/AN001_168") (pintype "bidirectional"))
    )
    (net (code "70") (name "unconnected-(U5-P0_2{slash}AN002-Pad167)") (class "Default")
      (node (ref "U5") (pin "167") (pinfunction "P0_2/AN002_167") (pintype "bidirectional"))
    )
    (net (code "71") (name "unconnected-(U5-P0_3{slash}PGAVSS000-Pad166)") (class "Default")
      (node (ref "U5") (pin "166") (pinfunction "P0_3/PGAVSS000_166") (pintype "bidirectional"))
    )
    (net (code "72") (name "unconnected-(U5-P0_4{slash}AN100-Pad165)") (class "Default")
      (node (ref "U5") (pin "165") (pinfunction "P0_4/AN100_165") (pintype "bidirectional"))
    )
    (net (code "73") (name "unconnected-(U5-P0_6{slash}AN102-Pad163)") (class "Default")
      (node (ref "U5") (pin "163") (pinfunction "P0_6/AN102_163") (pintype "bidirectional"))
    )
    (net (code "74") (name "unconnected-(U5-P0_7{slash}PGVSS100-Pad162)") (class "Default")
      (node (ref "U5") (pin "162") (pinfunction "P0_7/PGVSS100_162") (pintype "bidirectional"))
    )
    (net (code "75") (name "unconnected-(U5-P0_8{slash}AN003-Pad161)") (class "Default")
      (node (ref "U5") (pin "161") (pinfunction "P0_8/AN003_161") (pintype "bidirectional"))
    )
    (net (code "76") (name "unconnected-(U5-P0_9{slash}AN004-Pad160)") (class "Default")
      (node (ref "U5") (pin "160") (pinfunction "P0_9/AN004_160") (pintype "bidirectional"))
    )
    (net (code "77") (name "unconnected-(U5-P0_14{slash}DA0{slash}AN005{slash}AN105-Pad152)") (class "Default")
      (node (ref "U5") (pin "152") (pinfunction "P0_14/DA0/AN005/AN105_152") (pintype "bidirectional"))
    )
    (net (code "78") (name "unconnected-(U5-P0_15{slash}DA1{slash}AN006{slash}AN106-Pad151)") (class "Default")
      (node (ref "U5") (pin "151") (pinfunction "P0_15/DA1/AN006/AN106_151") (pintype "bidirectional"))
    )
    (net (code "79") (name "unconnected-(U5-P1_2-Pad130)") (class "Default")
      (node (ref "U5") (pin "130") (pinfunction "P1_2_130") (pintype "bidirectional"))
    )
    (net (code "80") (name "unconnected-(U5-P1_3-Pad129)") (class "Default")
      (node (ref "U5") (pin "129") (pinfunction "P1_3_129") (pintype "bidirectional"))
    )
    (net (code "81") (name "unconnected-(U5-P1_4-Pad128)") (class "Default")
      (node (ref "U5") (pin "128") (pinfunction "P1_4_128") (pintype "bidirectional"))
    )
    (net (code "82") (name "unconnected-(U5-P1_5-Pad127)") (class "Default")
      (node (ref "U5") (pin "127") (pinfunction "P1_5_127") (pintype "bidirectional"))
    )
    (net (code "83") (name "unconnected-(U5-P1_6-Pad126)") (class "Default")
      (node (ref "U5") (pin "126") (pinfunction "P1_6_126") (pintype "bidirectional"))
    )
    (net (code "84") (name "unconnected-(U5-P1_7-Pad125)") (class "Default")
      (node (ref "U5") (pin "125") (pinfunction "P1_7_125") (pintype "bidirectional"))
    )
    (net (code "85") (name "unconnected-(U5-P1_12-Pad93)") (class "Default")
      (node (ref "U5") (pin "93") (pinfunction "P1_12_93") (pintype "bidirectional"))
    )
    (net (code "86") (name "unconnected-(U5-P1_13-Pad94)") (class "Default")
      (node (ref "U5") (pin "94") (pinfunction "P1_13_94") (pintype "bidirectional"))
    )
    (net (code "87") (name "unconnected-(U5-P1_14-Pad95)") (class "Default")
      (node (ref "U5") (pin "95") (pinfunction "P1_14_95") (pintype "bidirectional"))
    )
    (net (code "88") (name "unconnected-(U5-P1_15-Pad96)") (class "Default")
      (node (ref "U5") (pin "96") (pinfunction "P1_15_96") (pintype "bidirectional"))
    )
    (net (code "89") (name "unconnected-(U5-P2_0(INPUT_ONLY)-Pad69)") (class "Default")
      (node (ref "U5") (pin "69") (pinfunction "P2_0(INPUT_ONLY)_69") (pintype "bidirectional"))
    )
    (net (code "90") (name "unconnected-(U5-P2_7-Pad49)") (class "Default")
      (node (ref "U5") (pin "49") (pinfunction "P2_7_49") (pintype "bidirectional"))
    )
    (net (code "91") (name "unconnected-(U5-P3_6-Pad80)") (class "Default")
      (node (ref "U5") (pin "80") (pinfunction "P3_6_80") (pintype "bidirectional"))
    )
    (net (code "92") (name "unconnected-(U5-P3_7-Pad79)") (class "Default")
      (node (ref "U5") (pin "79") (pinfunction "P3_7_79") (pintype "bidirectional"))
    )
    (net (code "93") (name "unconnected-(U5-P3_9-Pad77)") (class "Default")
      (node (ref "U5") (pin "77") (pinfunction "P3_9_77") (pintype "bidirectional"))
    )
    (net (code "94") (name "unconnected-(U5-P3_10-Pad76)") (class "Default")
      (node (ref "U5") (pin "76") (pinfunction "P3_10_76") (pintype "bidirectional"))
    )
    (net (code "95") (name "unconnected-(U5-P3_11-Pad75)") (class "Default")
      (node (ref "U5") (pin "75") (pinfunction "P3_11_75") (pintype "bidirectional"))
    )
    (net (code "96") (name "unconnected-(U5-P3_12-Pad74)") (class "Default")
      (node (ref "U5") (pin "74") (pinfunction "P3_12_74") (pintype "bidirectional"))
    )
    (net (code "97") (name "unconnected-(U5-P3_13-Pad55)") (class "Default")
      (node (ref "U5") (pin "55") (pinfunction "P3_13_55") (pintype "bidirectional"))
    )
    (net (code "98") (name "unconnected-(U5-P3_14-Pad56)") (class "Default")
      (node (ref "U5") (pin "56") (pinfunction "P3_14_56") (pintype "bidirectional"))
    )
    (net (code "99") (name "unconnected-(U5-P3_15-Pad57)") (class "Default")
      (node (ref "U5") (pin "57") (pinfunction "P3_15_57") (pintype "bidirectional"))
    )
    (net (code "100") (name "unconnected-(U5-P4_0-Pad1)") (class "Default")
      (node (ref "U5") (pin "1") (pinfunction "P4_0_1") (pintype "bidirectional"))
    )
    (net (code "101") (name "unconnected-(U5-P4_1-Pad2)") (class "Default")
      (node (ref "U5") (pin "2") (pinfunction "P4_1_2") (pintype "bidirectional"))
    )
    (net (code "102") (name "unconnected-(U5-P4_2-Pad3)") (class "Default")
      (node (ref "U5") (pin "3") (pinfunction "P4_2_3") (pintype "bidirectional"))
    )
    (net (code "103") (name "unconnected-(U5-P4_8-Pad43)") (class "Default")
      (node (ref "U5") (pin "43") (pinfunction "P4_8_43") (pintype "bidirectional"))
    )
    (net (code "104") (name "unconnected-(U5-P4_10-Pad41)") (class "Default")
      (node (ref "U5") (pin "41") (pinfunction "P4_10_41") (pintype "bidirectional"))
    )
    (net (code "105") (name "unconnected-(U5-P4_11-Pad40)") (class "Default")
      (node (ref "U5") (pin "40") (pinfunction "P4_11_40") (pintype "bidirectional"))
    )
    (net (code "106") (name "unconnected-(U5-P4_12-Pad39)") (class "Default")
      (node (ref "U5") (pin "39") (pinfunction "P4_12_39") (pintype "bidirectional"))
    )
    (net (code "107") (name "unconnected-(U5-P4_13-Pad38)") (class "Default")
      (node (ref "U5") (pin "38") (pinfunction "P4_13_38") (pintype "bidirectional"))
    )
    (net (code "108") (name "unconnected-(U5-P4_14-Pad37)") (class "Default")
      (node (ref "U5") (pin "37") (pinfunction "P4_14_37") (pintype "bidirectional"))
    )
    (net (code "109") (name "unconnected-(U5-P4_15-Pad36)") (class "Default")
      (node (ref "U5") (pin "36") (pinfunction "P4_15_36") (pintype "bidirectional"))
    )
    (net (code "110") (name "unconnected-(U5-P5_0{slash}AN016-Pad140)") (class "Default")
      (node (ref "U5") (pin "140") (pinfunction "P5_0/AN016_140") (pintype "bidirectional"))
    )
    (net (code "111") (name "unconnected-(U5-P5_1{slash}AN116-Pad141)") (class "Default")
      (node (ref "U5") (pin "141") (pinfunction "P5_1/AN116_141") (pintype "bidirectional"))
    )
    (net (code "112") (name "unconnected-(U5-P5_2{slash}AN017-Pad142)") (class "Default")
      (node (ref "U5") (pin "142") (pinfunction "P5_2/AN017_142") (pintype "bidirectional"))
    )
    (net (code "113") (name "unconnected-(U5-P5_3{slash}AN117-Pad143)") (class "Default")
      (node (ref "U5") (pin "143") (pinfunction "P5_3/AN117_143") (pintype "bidirectional"))
    )
    (net (code "114") (name "unconnected-(U5-P5_4{slash}AN018-Pad144)") (class "Default")
      (node (ref "U5") (pin "144") (pinfunction "P5_4/AN018_144") (pintype "bidirectional"))
    )
    (net (code "115") (name "unconnected-(U5-P5_5{slash}AN118-Pad145)") (class "Default")
      (node (ref "U5") (pin "145") (pinfunction "P5_5/AN118_145") (pintype "bidirectional"))
    )
    (net (code "116") (name "unconnected-(U5-P5_6{slash}AN019-Pad146)") (class "Default")
      (node (ref "U5") (pin "146") (pinfunction "P5_6/AN019_146") (pintype "bidirectional"))
    )
    (net (code "117") (name "unconnected-(U5-P5_7{slash}AN119-Pad147)") (class "Default")
      (node (ref "U5") (pin "147") (pinfunction "P5_7/AN119_147") (pintype "bidirectional"))
    )
    (net (code "118") (name "unconnected-(U5-P5_11-Pad176)") (class "Default")
      (node (ref "U5") (pin "176") (pinfunction "P5_11_176") (pintype "bidirectional"))
    )
    (net (code "119") (name "unconnected-(U5-P5_13-Pad174)") (class "Default")
      (node (ref "U5") (pin "174") (pinfunction "P5_13_174") (pintype "bidirectional"))
    )
    (net (code "120") (name "unconnected-(U5-P6_0-Pad122)") (class "Default")
      (node (ref "U5") (pin "122") (pinfunction "P6_0_122") (pintype "bidirectional"))
    )
    (net (code "121") (name "unconnected-(U5-P6_2-Pad120)") (class "Default")
      (node (ref "U5") (pin "120") (pinfunction "P6_2_120") (pintype "bidirectional"))
    )
    (net (code "122") (name "unconnected-(U5-P6_3-Pad119)") (class "Default")
      (node (ref "U5") (pin "119") (pinfunction "P6_3_119") (pintype "bidirectional"))
    )
    (net (code "123") (name "unconnected-(U5-P6_5-Pad117)") (class "Default")
      (node (ref "U5") (pin "117") (pinfunction "P6_5_117") (pintype "bidirectional"))
    )
    (net (code "124") (name "unconnected-(U5-P6_6-Pad116)") (class "Default")
      (node (ref "U5") (pin "116") (pinfunction "P6_6_116") (pintype "bidirectional"))
    )
    (net (code "125") (name "unconnected-(U5-P6_8-Pad99)") (class "Default")
      (node (ref "U5") (pin "99") (pinfunction "P6_8_99") (pintype "bidirectional"))
    )
    (net (code "126") (name "unconnected-(U5-P6_9-Pad100)") (class "Default")
      (node (ref "U5") (pin "100") (pinfunction "P6_9_100") (pintype "bidirectional"))
    )
    (net (code "127") (name "unconnected-(U5-P6_11-Pad102)") (class "Default")
      (node (ref "U5") (pin "102") (pinfunction "P6_11_102") (pintype "bidirectional"))
    )
    (net (code "128") (name "unconnected-(U5-P6_12-Pad103)") (class "Default")
      (node (ref "U5") (pin "103") (pinfunction "P6_12_103") (pintype "bidirectional"))
    )
    (net (code "129") (name "unconnected-(U5-P6_13-Pad104)") (class "Default")
      (node (ref "U5") (pin "104") (pinfunction "P6_13_104") (pintype "bidirectional"))
    )
    (net (code "130") (name "unconnected-(U5-P6_14-Pad105)") (class "Default")
      (node (ref "U5") (pin "105") (pinfunction "P6_14_105") (pintype "bidirectional"))
    )
    (net (code "131") (name "unconnected-(U5-P6_15-Pad106)") (class "Default")
      (node (ref "U5") (pin "106") (pinfunction "P6_15_106") (pintype "bidirectional"))
    )
    (net (code "132") (name "unconnected-(U5-P7_6-Pad14)") (class "Default")
      (node (ref "U5") (pin "14") (pinfunction "P7_6_14") (pintype "bidirectional"))
    )
    (net (code "133") (name "unconnected-(U5-P7_7-Pad15)") (class "Default")
      (node (ref "U5") (pin "15") (pinfunction "P7_7_15") (pintype "bidirectional"))
    )
    (net (code "134") (name "unconnected-(U5-P8_0-Pad133)") (class "Default")
      (node (ref "U5") (pin "133") (pinfunction "P8_0_133") (pintype "bidirectional"))
    )
    (net (code "135") (name "unconnected-(U5-P8_1-Pad134)") (class "Default")
      (node (ref "U5") (pin "134") (pinfunction "P8_1_134") (pintype "bidirectional"))
    )
    (net (code "136") (name "unconnected-(U5-P8_2-Pad135)") (class "Default")
      (node (ref "U5") (pin "135") (pinfunction "P8_2_135") (pintype "bidirectional"))
    )
    (net (code "137") (name "unconnected-(U5-P8_3-Pad136)") (class "Default")
      (node (ref "U5") (pin "136") (pinfunction "P8_3_136") (pintype "bidirectional"))
    )
    (net (code "138") (name "unconnected-(U5-P8_4-Pad137)") (class "Default")
      (node (ref "U5") (pin "137") (pinfunction "P8_4_137") (pintype "bidirectional"))
    )
    (net (code "139") (name "unconnected-(U5-P8_5-Pad173)") (class "Default")
      (node (ref "U5") (pin "173") (pinfunction "P8_5_173") (pintype "bidirectional"))
    )
    (net (code "140") (name "unconnected-(U5-P9_0-Pad58)") (class "Default")
      (node (ref "U5") (pin "58") (pinfunction "P9_0_58") (pintype "bidirectional"))
    )
    (net (code "141") (name "unconnected-(U5-P9_1-Pad59)") (class "Default")
      (node (ref "U5") (pin "59") (pinfunction "P9_1_59") (pintype "bidirectional"))
    )
    (net (code "142") (name "unconnected-(U5-P9_5-Pad73)") (class "Default")
      (node (ref "U5") (pin "73") (pinfunction "P9_5_73") (pintype "bidirectional"))
    )
    (net (code "143") (name "unconnected-(U5-P9_6-Pad72)") (class "Default")
      (node (ref "U5") (pin "72") (pinfunction "P9_6_72") (pintype "bidirectional"))
    )
    (net (code "144") (name "unconnected-(U5-P9_7-Pad71)") (class "Default")
      (node (ref "U5") (pin "71") (pinfunction "P9_7_71") (pintype "bidirectional"))
    )
    (net (code "145") (name "unconnected-(U5-P9_8-Pad70)") (class "Default")
      (node (ref "U5") (pin "70") (pinfunction "P9_8_70") (pintype "bidirectional"))
    )
    (net (code "146") (name "unconnected-(U5-PA_0-Pad114)") (class "Default")
      (node (ref "U5") (pin "114") (pinfunction "PA_0_114") (pintype "bidirectional"))
    )
    (net (code "147") (name "unconnected-(U5-PA_1-Pad113)") (class "Default")
      (node (ref "U5") (pin "113") (pinfunction "PA_1_113") (pintype "bidirectional"))
    )
    (net (code "148") (name "unconnected-(U5-PA_8-Pad107)") (class "Default")
      (node (ref "U5") (pin "107") (pinfunction "PA_8_107") (pintype "bidirectional"))
    )
    (net (code "149") (name "unconnected-(U5-PA_9-Pad108)") (class "Default")
      (node (ref "U5") (pin "108") (pinfunction "PA_9_108") (pintype "bidirectional"))
    )
    (net (code "150") (name "unconnected-(U5-PA_10-Pad109)") (class "Default")
      (node (ref "U5") (pin "109") (pinfunction "PA_10_109") (pintype "bidirectional"))
    )
    (net (code "151") (name "unconnected-(U5-VBAT-Pad18)") (class "Default")
      (node (ref "U5") (pin "18") (pinfunction "VBAT_18") (pintype "bidirectional"))
    )
    (net (code "152") (name "unconnected-(U5-VREFH-Pad154)") (class "Default")
      (node (ref "U5") (pin "154") (pinfunction "VREFH_154") (pintype "bidirectional"))
    )
    (net (code "153") (name "unconnected-(U5-VREFH0-Pad158)") (class "Default")
      (node (ref "U5") (pin "158") (pinfunction "VREFH0_158") (pintype "bidirectional"))
    )
    (net (code "154") (name "unconnected-(U5-VREFL-Pad153)") (class "Default")
      (node (ref "U5") (pin "153") (pinfunction "VREFL_153") (pintype "bidirectional"))
    )
    (net (code "155") (name "unconnected-(U5-VREFL0-Pad157)") (class "Default")
      (node (ref "U5") (pin "157") (pinfunction "VREFL0_157") (pintype "bidirectional"))
    )
  )
)
